# Alimentation.net
KiCad netlist of a schematic drawn in Altium Designer
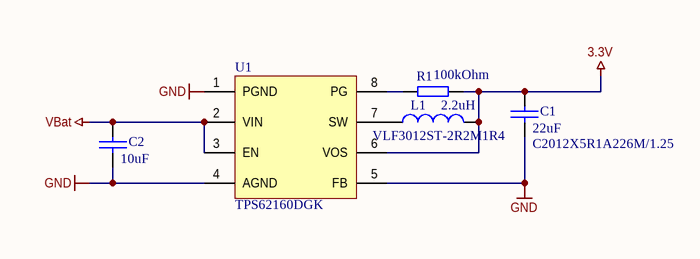
[diagram p0: Alimentation.SchDoc]

(export (version "E")
  (design (tool "Eeschema 10.0.6"))
  (components
    (comp (ref "C1")
      (value "C2012X5R1A226M/1.25")
      (footprint "080501")
      (description "CAPA")
      (fields (field (name "ALTIUM_VALUE") "22uF"))
      (libsource (lib "General-Sch-205") (part "CAPA"))
    )
    (comp (ref "C2")
      (value "10uF")
      (footprint "080501")
      (description "CAPA")
      (fields (field (name "Comment") "GRM21BR61E106KA73L"))
      (libsource (lib "General-Sch-205") (part "CAPA"))
    )
    (comp (ref "L1")
      (value "VLF3012ST-2R2M1R4")
      (footprint "InductanceAlim")
      (fields (field (name "ALTIUM_VALUE") "2.2uH"))
      (libsource (lib "General-Sch-205") (part "INDUCTOR"))
    )
    (comp (ref "R1")
      (value "100kOhm")
      (footprint "080501")
      (fields (field (name "Comment") "ERJ-6GEYJ104V"))
      (libsource (lib "General-Sch-205") (part "RES"))
    )
    (comp (ref "U1")
      (value "TPS62160DGK")
      (footprint "TSOP65P490-8AM")
      (description "IC BUCK SYNC ADJ 1A 8MSOP")
      (libsource (lib "Schlib1") (part "TPS62160"))
    )
  )
  (nets
    (net (code "1") (name "3.3V") (class "Default")
      (node (ref "C1") (pin "1") (pintype "passive"))
      (node (ref "L1") (pin "2") (pintype "passive"))
      (node (ref "R1") (pin "2") (pintype "passive"))
      (node (ref "U1") (pin "6") (pinfunction "VOS_6") (pintype "passive"))
    )
    (net (code "2") (name "GND") (class "Default")
      (node (ref "C1") (pin "2") (pintype "passive"))
      (node (ref "C2") (pin "2") (pintype "passive"))
      (node (ref "U1") (pin "1") (pinfunction "PGND_1") (pintype "passive"))
      (node (ref "U1") (pin "4") (pinfunction "AGND_4") (pintype "passive"))
      (node (ref "U1") (pin "5") (pinfunction "FB_5") (pintype "passive"))
    )
    (net (code "3") (name "Net-(U1-PG)") (class "Default")
      (node (ref "R1") (pin "1") (pintype "passive"))
      (node (ref "U1") (pin "8") (pinfunction "PG_8") (pintype "passive"))
    )
    (net (code "4") (name "Net-(U1-SW)") (class "Default")
      (node (ref "L1") (pin "1") (pintype "passive"))
      (node (ref "U1") (pin "7") (pinfunction "SW_7") (pintype "passive"))
    )
    (net (code "5") (name "VBat") (class "Default")
      (node (ref "C2") (pin "1") (pintype "passive"))
      (node (ref "U1") (pin "2") (pinfunction "VIN_2") (pintype "passive"))
      (node (ref "U1") (pin "3") (pinfunction "EN_3") (pintype "passive"))
    )
  )
)
